# DDS_rev02.net
KiCad netlist of a schematic drawn in EAGLE
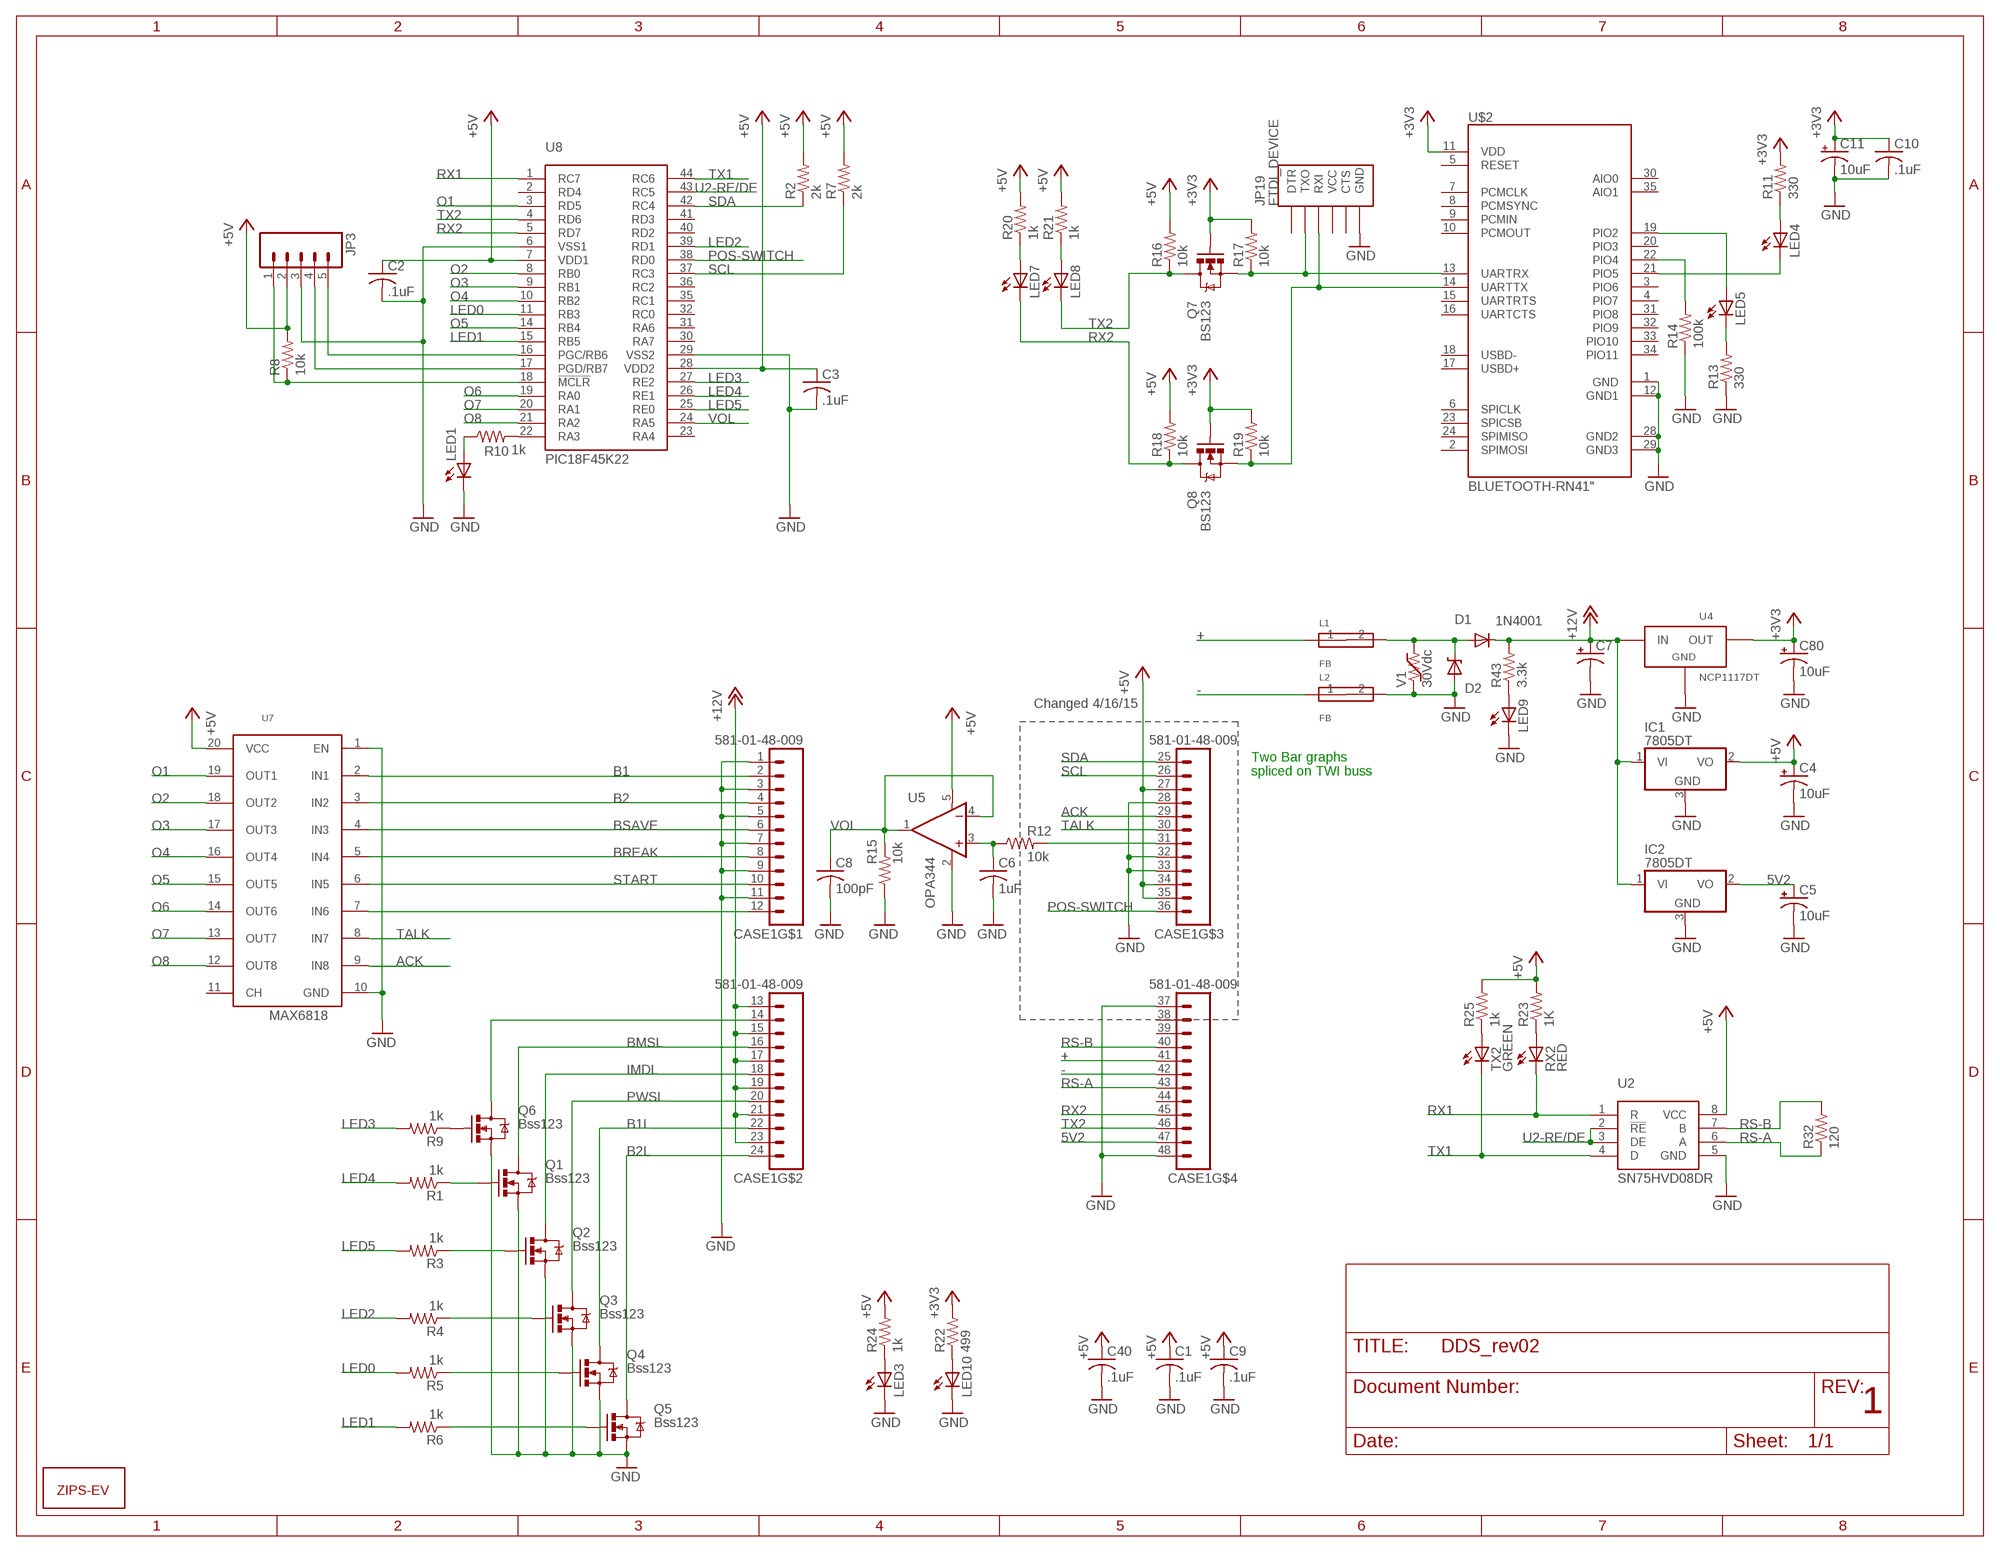
[diagram p0: schematic, sheet 1]

(export (version "E")
  (design (tool "Eeschema 10.0.6"))
  (components
    (comp (ref "C1")
      (value ".1uF")
      (footprint "eagle-import:C0805")
      (libsource (lib "eagle-import") (part "C-USC0805"))
    )
    (comp (ref "C2")
      (value ".1uF")
      (footprint "eagle-import:C0805")
      (libsource (lib "eagle-import") (part "C-USC0805"))
    )
    (comp (ref "C3")
      (value ".1uF")
      (footprint "eagle-import:C0805")
      (libsource (lib "eagle-import") (part "C-USC0805"))
    )
    (comp (ref "C4")
      (value "10uF")
      (footprint "eagle-import:POLC1206")
      (libsource (lib "eagle-import") (part "POLCAP"))
    )
    (comp (ref "C5")
      (value "10uF")
      (footprint "eagle-import:POLC1206")
      (libsource (lib "eagle-import") (part "POLCAP"))
    )
    (comp (ref "C6")
      (value "1uF")
      (footprint "eagle-import:C0805")
      (libsource (lib "eagle-import") (part "C-USC0805"))
    )
    (comp (ref "C7")
      (value "CAP_POL7343")
      (footprint "eagle-import:EIA7343")
      (libsource (lib "eagle-import") (part "CAP_POL7343"))
    )
    (comp (ref "C8")
      (value "100pF")
      (footprint "eagle-import:C0805")
      (libsource (lib "eagle-import") (part "C-USC0805"))
    )
    (comp (ref "C9")
      (value ".1uF")
      (footprint "eagle-import:C0805")
      (libsource (lib "eagle-import") (part "C-USC0805"))
    )
    (comp (ref "C10")
      (value ".1uF")
      (footprint "eagle-import:C0805")
      (libsource (lib "eagle-import") (part "C-USC0805"))
    )
    (comp (ref "C11")
      (value "10uF")
      (footprint "eagle-import:POLC1206")
      (libsource (lib "eagle-import") (part "POLCAP"))
    )
    (comp (ref "C40")
      (value ".1uF")
      (footprint "eagle-import:C0805")
      (libsource (lib "eagle-import") (part "C-USC0805"))
    )
    (comp (ref "C80")
      (value "10uF")
      (footprint "eagle-import:POLC1206")
      (libsource (lib "eagle-import") (part "POLCAP"))
    )
    (comp (ref "CASE1")
      (value "581-01-48-009")
      (footprint "eagle-import:581-01-48-009")
      (libsource (lib "eagle-import") (part "581-01-48-009"))
    )
    (comp (ref "D1")
      (value "1N4001")
      (footprint "eagle-import:SOD123")
      (libsource (lib "eagle-import") (part "DIODE-SOD123"))
    )
    (comp (ref "D2")
      (value "MM5Z30")
      (footprint "eagle-import:SOD-523F")
      (libsource (lib "eagle-import") (part "MM5Z30"))
    )
    (comp (ref "IC1")
      (value "7805DT")
      (footprint "eagle-import:TO252")
      (libsource (lib "eagle-import") (part "78DT05"))
    )
    (comp (ref "IC2")
      (value "7805DT")
      (footprint "eagle-import:TO252")
      (libsource (lib "eagle-import") (part "78DT05"))
    )
    (comp (ref "JP3")
      (value "M05LOCK_LONGPADS")
      (footprint "eagle-import:1X05_LOCK_LONGPADS")
      (libsource (lib "eagle-import") (part "M05LOCK_LONGPADS"))
    )
    (comp (ref "JP19")
      (value "FTDI_DEVICE")
      (footprint "eagle-import:FTDI_DEVICE_SIDE")
      (libsource (lib "eagle-import") (part "FTDI_DEVICE"))
    )
    (comp (ref "L1")
      (value "FB")
      (footprint "eagle-import:0603")
      (libsource (lib "eagle-import") (part "FERITEBEAD"))
    )
    (comp (ref "L2")
      (value "FB")
      (footprint "eagle-import:0603")
      (libsource (lib "eagle-import") (part "FERITEBEAD"))
    )
    (comp (ref "LED1")
      (value "LEDCHIP-LED0805")
      (footprint "eagle-import:CHIP-LED0805")
      (libsource (lib "eagle-import") (part "LEDCHIP-LED0805"))
    )
    (comp (ref "LED3")
      (value "LEDCHIP-LED0805")
      (footprint "eagle-import:CHIP-LED0805")
      (libsource (lib "eagle-import") (part "LEDCHIP-LED0805"))
    )
    (comp (ref "LED4")
      (value "LEDCHIP-LED0805")
      (footprint "eagle-import:CHIP-LED0805")
      (libsource (lib "eagle-import") (part "led_LEDCHIP-LED0805"))
    )
    (comp (ref "LED5")
      (value "LEDCHIP-LED0805")
      (footprint "eagle-import:CHIP-LED0805")
      (libsource (lib "eagle-import") (part "led_LEDCHIP-LED0805"))
    )
    (comp (ref "LED7")
      (value "LEDCHIP-LED0805")
      (footprint "eagle-import:CHIP-LED0805")
      (libsource (lib "eagle-import") (part "led_LEDCHIP-LED0805"))
    )
    (comp (ref "LED8")
      (value "LEDCHIP-LED0805")
      (footprint "eagle-import:CHIP-LED0805")
      (libsource (lib "eagle-import") (part "led_LEDCHIP-LED0805"))
    )
    (comp (ref "LED9")
      (value "LEDCHIP-LED0805")
      (footprint "eagle-import:CHIP-LED0805")
      (libsource (lib "eagle-import") (part "LEDCHIP-LED0805"))
    )
    (comp (ref "LED10")
      (value "LEDCHIP-LED0805")
      (footprint "eagle-import:CHIP-LED0805")
      (libsource (lib "eagle-import") (part "LEDCHIP-LED0805"))
    )
    (comp (ref "Q1")
      (value "Bss123")
      (footprint "eagle-import:SOT23")
      (libsource (lib "eagle-import") (part "MOSFET-NCHANNELBSS123LT1G"))
    )
    (comp (ref "Q2")
      (value "Bss123")
      (footprint "eagle-import:SOT23")
      (libsource (lib "eagle-import") (part "MOSFET-NCHANNELBSS123LT1G"))
    )
    (comp (ref "Q3")
      (value "Bss123")
      (footprint "eagle-import:SOT23")
      (libsource (lib "eagle-import") (part "MOSFET-NCHANNELBSS123LT1G"))
    )
    (comp (ref "Q4")
      (value "Bss123")
      (footprint "eagle-import:SOT23")
      (libsource (lib "eagle-import") (part "MOSFET-NCHANNELBSS123LT1G"))
    )
    (comp (ref "Q5")
      (value "Bss123")
      (footprint "eagle-import:SOT23")
      (libsource (lib "eagle-import") (part "MOSFET-NCHANNELBSS123LT1G"))
    )
    (comp (ref "Q6")
      (value "Bss123")
      (footprint "eagle-import:SOT23")
      (libsource (lib "eagle-import") (part "MOSFET-NCHANNELBSS123LT1G"))
    )
    (comp (ref "Q7")
      (value "BS123")
      (footprint "eagle-import:SOT23")
      (libsource (lib "eagle-import") (part "MOSFET-NCHANNELBSS123LT1G"))
    )
    (comp (ref "Q8")
      (value "BS123")
      (footprint "eagle-import:SOT23")
      (libsource (lib "eagle-import") (part "MOSFET-NCHANNELBSS123LT1G"))
    )
    (comp (ref "R1")
      (value "1k")
      (footprint "eagle-import:R0805")
      (libsource (lib "eagle-import") (part "R-US_R0805"))
    )
    (comp (ref "R2")
      (value "2k")
      (footprint "eagle-import:R0805")
      (libsource (lib "eagle-import") (part "R-US_R0805"))
    )
    (comp (ref "R3")
      (value "1k")
      (footprint "eagle-import:R0805")
      (libsource (lib "eagle-import") (part "R-US_R0805"))
    )
    (comp (ref "R4")
      (value "1k")
      (footprint "eagle-import:R0805")
      (libsource (lib "eagle-import") (part "R-US_R0805"))
    )
    (comp (ref "R5")
      (value "1k")
      (footprint "eagle-import:R0805")
      (libsource (lib "eagle-import") (part "R-US_R0805"))
    )
    (comp (ref "R6")
      (value "1k")
      (footprint "eagle-import:R0805")
      (libsource (lib "eagle-import") (part "R-US_R0805"))
    )
    (comp (ref "R7")
      (value "2k")
      (footprint "eagle-import:R0805")
      (libsource (lib "eagle-import") (part "R-US_R0805"))
    )
    (comp (ref "R8")
      (value "10k")
      (footprint "eagle-import:0805")
      (libsource (lib "eagle-import") (part "RESISTOR0805-RES"))
    )
    (comp (ref "R9")
      (value "1k")
      (footprint "eagle-import:R0805")
      (libsource (lib "eagle-import") (part "R-US_R0805"))
    )
    (comp (ref "R10")
      (value "1k")
      (footprint "eagle-import:R0805")
      (libsource (lib "eagle-import") (part "R-US_R0805"))
    )
    (comp (ref "R11")
      (value "330")
      (footprint "eagle-import:0805")
      (libsource (lib "eagle-import") (part "RESISTOR0805-RES"))
    )
    (comp (ref "R12")
      (value "10k")
      (footprint "eagle-import:R0805")
      (libsource (lib "eagle-import") (part "R-US_R0805"))
    )
    (comp (ref "R13")
      (value "330")
      (footprint "eagle-import:0805")
      (libsource (lib "eagle-import") (part "RESISTOR0805-RES"))
    )
    (comp (ref "R14")
      (value "100k")
      (footprint "eagle-import:0805")
      (libsource (lib "eagle-import") (part "RESISTOR0805-RES"))
    )
    (comp (ref "R15")
      (value "10k")
      (footprint "eagle-import:R0805")
      (libsource (lib "eagle-import") (part "R-US_R0805"))
    )
    (comp (ref "R16")
      (value "10k")
      (footprint "eagle-import:0805")
      (libsource (lib "eagle-import") (part "RESISTOR0805-RES"))
    )
    (comp (ref "R17")
      (value "10k")
      (footprint "eagle-import:0805")
      (libsource (lib "eagle-import") (part "RESISTOR0805-RES"))
    )
    (comp (ref "R18")
      (value "10k")
      (footprint "eagle-import:0805")
      (libsource (lib "eagle-import") (part "RESISTOR0805-RES"))
    )
    (comp (ref "R19")
      (value "10k")
      (footprint "eagle-import:0805")
      (libsource (lib "eagle-import") (part "RESISTOR0805-RES"))
    )
    (comp (ref "R20")
      (value "1k")
      (footprint "eagle-import:0805")
      (libsource (lib "eagle-import") (part "RESISTOR0805-RES"))
    )
    (comp (ref "R21")
      (value "1k")
      (footprint "eagle-import:0805")
      (libsource (lib "eagle-import") (part "RESISTOR0805-RES"))
    )
    (comp (ref "R22")
      (value "499")
      (footprint "eagle-import:R0805")
      (libsource (lib "eagle-import") (part "R-US_R0805"))
    )
    (comp (ref "R23")
      (value "1K")
      (footprint "eagle-import:R0805")
      (libsource (lib "eagle-import") (part "R-US_R0805"))
    )
    (comp (ref "R24")
      (value "1k")
      (footprint "eagle-import:R0805")
      (libsource (lib "eagle-import") (part "R-US_R0805"))
    )
    (comp (ref "R25")
      (value "1k")
      (footprint "eagle-import:R0805")
      (libsource (lib "eagle-import") (part "R-US_R0805"))
    )
    (comp (ref "R32")
      (value "120")
      (footprint "eagle-import:R0805")
      (libsource (lib "eagle-import") (part "R-US_R0805"))
    )
    (comp (ref "R43")
      (value "3.3k")
      (footprint "eagle-import:R0805")
      (libsource (lib "eagle-import") (part "R-US_R0805"))
    )
    (comp (ref "RX2")
      (value "RED")
      (footprint "eagle-import:CHIPLED_0805")
      (libsource (lib "eagle-import") (part "LEDCHIPLED_0805"))
    )
    (comp (ref "TX2")
      (value "GREEN")
      (footprint "eagle-import:CHIPLED_0805")
      (libsource (lib "eagle-import") (part "LEDCHIPLED_0805"))
    )
    (comp (ref "U$1")
      (value "LOGO")
      (footprint "eagle-import:L-L")
      (libsource (lib "eagle-import") (part "LOGO"))
    )
    (comp (ref "U$2")
      (value "BLUETOOTH-RN41\"")
      (footprint "eagle-import:RN41")
      (libsource (lib "eagle-import") (part "BLUETOOTH-RN41{dblquote}"))
    )
    (comp (ref "U2")
      (value "SN75HVD08DR")
      (footprint "eagle-import:SO-8")
      (libsource (lib "eagle-import") (part "SN75HVD08DR"))
    )
    (comp (ref "U4")
      (value "NCP1117DT")
      (footprint "eagle-import:DPAK")
      (libsource (lib "eagle-import") (part "NCP1117DT"))
    )
    (comp (ref "U5")
      (value "OPA344")
      (footprint "eagle-import:SOT23-5")
      (libsource (lib "eagle-import") (part "OPA344"))
    )
    (comp (ref "U7")
      (value "MAX6818")
      (footprint "eagle-import:SSOP-20")
      (libsource (lib "eagle-import") (part "MAX6818"))
    )
    (comp (ref "U8")
      (value "PIC18F45K22")
      (footprint "eagle-import:TQFP-44")
      (libsource (lib "eagle-import") (part "PIC18F45K22"))
    )
    (comp (ref "V1")
      (value "30Vdc")
      (footprint "eagle-import:0603")
      (libsource (lib "eagle-import") (part "VAR-RES"))
    )
  )
  (nets
    (net (code "1") (name "+3V3") (class "Default")
      (node (ref "C10") (pin "1") (pinfunction "1_1") (pintype "passive"))
      (node (ref "C11") (pin "1") (pinfunction "+_1") (pintype "passive"))
      (node (ref "C80") (pin "1") (pinfunction "+_1") (pintype "passive"))
      (node (ref "Q7") (pin "1") (pinfunction "G_1") (pintype "passive"))
      (node (ref "Q8") (pin "1") (pinfunction "G_1") (pintype "passive"))
      (node (ref "R11") (pin "2") (pinfunction "2_2") (pintype "passive"))
      (node (ref "R17") (pin "2") (pinfunction "2_2") (pintype "passive"))
      (node (ref "R19") (pin "2") (pinfunction "2_2") (pintype "passive"))
      (node (ref "R22") (pin "2") (pinfunction "2_2") (pintype "passive"))
      (node (ref "U$2") (pin "11") (pinfunction "VDD_11") (pintype "bidirectional"))
      (node (ref "U4") (pin "2") (pinfunction "OUT_2") (pintype "bidirectional"))
    )
    (net (code "2") (name "+5V") (class "Default")
      (node (ref "C1") (pin "1") (pinfunction "1_1") (pintype "passive"))
      (node (ref "C2") (pin "1") (pinfunction "1_1") (pintype "passive"))
      (node (ref "C3") (pin "1") (pinfunction "1_1") (pintype "passive"))
      (node (ref "C4") (pin "1") (pinfunction "+_1") (pintype "passive"))
      (node (ref "C40") (pin "1") (pinfunction "1_1") (pintype "passive"))
      (node (ref "C9") (pin "1") (pinfunction "1_1") (pintype "passive"))
      (node (ref "CASE1") (pin "27") (pinfunction "3_27") (pintype "passive"))
      (node (ref "CASE1") (pin "34") (pinfunction "10_34") (pintype "passive"))
      (node (ref "CASE1") (pin "35") (pinfunction "11_35") (pintype "passive"))
      (node (ref "IC1") (pin "2") (pinfunction "VO_2") (pintype "passive"))
      (node (ref "JP3") (pin "2") (pinfunction "2_2") (pintype "passive"))
      (node (ref "R16") (pin "2") (pinfunction "2_2") (pintype "passive"))
      (node (ref "R18") (pin "2") (pinfunction "2_2") (pintype "passive"))
      (node (ref "R2") (pin "2") (pinfunction "2_2") (pintype "passive"))
      (node (ref "R20") (pin "2") (pinfunction "2_2") (pintype "passive"))
      (node (ref "R21") (pin "2") (pinfunction "2_2") (pintype "passive"))
      (node (ref "R23") (pin "2") (pinfunction "2_2") (pintype "passive"))
      (node (ref "R24") (pin "2") (pinfunction "2_2") (pintype "passive"))
      (node (ref "R25") (pin "2") (pinfunction "2_2") (pintype "passive"))
      (node (ref "R7") (pin "2") (pinfunction "2_2") (pintype "passive"))
      (node (ref "R8") (pin "2") (pinfunction "2_2") (pintype "passive"))
      (node (ref "U2") (pin "8") (pinfunction "VCC_8") (pintype "bidirectional"))
      (node (ref "U5") (pin "5") (pinfunction "V+_5") (pintype "power_in"))
      (node (ref "U7") (pin "20") (pinfunction "VCC_20") (pintype "bidirectional"))
      (node (ref "U8") (pin "28") (pinfunction "VDD2_28") (pintype "bidirectional"))
      (node (ref "U8") (pin "7") (pinfunction "VDD1_7") (pintype "bidirectional"))
    )
    (net (code "3") (name "+12V") (class "Default")
      (node (ref "C7") (pin "A") (pinfunction "+_A") (pintype "passive"))
      (node (ref "CASE1") (pin "13") (pinfunction "1_13") (pintype "passive"))
      (node (ref "CASE1") (pin "15") (pinfunction "3_15") (pintype "passive"))
      (node (ref "CASE1") (pin "17") (pinfunction "5_17") (pintype "passive"))
      (node (ref "CASE1") (pin "19") (pinfunction "7_19") (pintype "passive"))
      (node (ref "CASE1") (pin "21") (pinfunction "9_21") (pintype "passive"))
      (node (ref "CASE1") (pin "23") (pinfunction "11_23") (pintype "passive"))
      (node (ref "D1") (pin "C") (pinfunction "C_C") (pintype "passive"))
      (node (ref "IC1") (pin "1") (pinfunction "VI_1") (pintype "input"))
      (node (ref "IC2") (pin "1") (pinfunction "VI_1") (pintype "input"))
      (node (ref "R43") (pin "2") (pinfunction "2_2") (pintype "passive"))
      (node (ref "U4") (pin "3") (pinfunction "IN_3") (pintype "bidirectional"))
    )
    (net (code "4") (name "/+") (class "Default")
      (node (ref "CASE1") (pin "41") (pinfunction "5_41") (pintype "passive"))
      (node (ref "L1") (pin "1") (pinfunction "P$1_1") (pintype "bidirectional"))
    )
    (net (code "5") (name "/-") (class "Default")
      (node (ref "CASE1") (pin "42") (pinfunction "6_42") (pintype "passive"))
      (node (ref "L2") (pin "1") (pinfunction "P$1_1") (pintype "bidirectional"))
    )
    (net (code "6") (name "/5V2") (class "Default")
      (node (ref "C5") (pin "1") (pinfunction "+_1") (pintype "passive"))
      (node (ref "CASE1") (pin "47") (pinfunction "11_47") (pintype "passive"))
      (node (ref "IC2") (pin "2") (pinfunction "VO_2") (pintype "passive"))
    )
    (net (code "7") (name "/ACK") (class "Default")
      (node (ref "CASE1") (pin "29") (pinfunction "5_29") (pintype "passive"))
      (node (ref "U7") (pin "9") (pinfunction "IN8_9") (pintype "bidirectional"))
    )
    (net (code "8") (name "/B1") (class "Default")
      (node (ref "CASE1") (pin "2") (pinfunction "2_2") (pintype "passive"))
      (node (ref "U7") (pin "2") (pinfunction "IN1_2") (pintype "bidirectional"))
    )
    (net (code "9") (name "/B1L") (class "Default")
      (node (ref "CASE1") (pin "22") (pinfunction "10_22") (pintype "passive"))
      (node (ref "Q4") (pin "3") (pinfunction "D_3") (pintype "passive"))
    )
    (net (code "10") (name "/B2") (class "Default")
      (node (ref "CASE1") (pin "4") (pinfunction "4_4") (pintype "passive"))
      (node (ref "U7") (pin "3") (pinfunction "IN2_3") (pintype "bidirectional"))
    )
    (net (code "11") (name "/B2L") (class "Default")
      (node (ref "CASE1") (pin "24") (pinfunction "12_24") (pintype "passive"))
      (node (ref "Q5") (pin "3") (pinfunction "D_3") (pintype "passive"))
    )
    (net (code "12") (name "/BMSL") (class "Default")
      (node (ref "CASE1") (pin "16") (pinfunction "4_16") (pintype "passive"))
      (node (ref "Q1") (pin "3") (pinfunction "D_3") (pintype "passive"))
    )
    (net (code "13") (name "/BREAK") (class "Default")
      (node (ref "CASE1") (pin "8") (pinfunction "8_8") (pintype "passive"))
      (node (ref "U7") (pin "5") (pinfunction "IN4_5") (pintype "bidirectional"))
    )
    (net (code "14") (name "/BSAVE") (class "Default")
      (node (ref "CASE1") (pin "6") (pinfunction "6_6") (pintype "passive"))
      (node (ref "U7") (pin "4") (pinfunction "IN3_4") (pintype "bidirectional"))
    )
    (net (code "15") (name "/IMDL") (class "Default")
      (node (ref "CASE1") (pin "18") (pinfunction "6_18") (pintype "passive"))
      (node (ref "Q2") (pin "3") (pinfunction "D_3") (pintype "passive"))
    )
    (net (code "16") (name "/LED0") (class "Default")
      (node (ref "R5") (pin "2") (pinfunction "2_2") (pintype "passive"))
      (node (ref "U8") (pin "11") (pinfunction "RB3_11") (pintype "bidirectional"))
    )
    (net (code "17") (name "/LED1") (class "Default")
      (node (ref "R6") (pin "2") (pinfunction "2_2") (pintype "passive"))
      (node (ref "U8") (pin "15") (pinfunction "RB5_15") (pintype "bidirectional"))
    )
    (net (code "18") (name "/LED2") (class "Default")
      (node (ref "R4") (pin "2") (pinfunction "2_2") (pintype "passive"))
      (node (ref "U8") (pin "39") (pinfunction "RD1_39") (pintype "bidirectional"))
    )
    (net (code "19") (name "/LED3") (class "Default")
      (node (ref "R9") (pin "2") (pinfunction "2_2") (pintype "passive"))
      (node (ref "U8") (pin "27") (pinfunction "RE2_27") (pintype "bidirectional"))
    )
    (net (code "20") (name "/LED4") (class "Default")
      (node (ref "R1") (pin "2") (pinfunction "2_2") (pintype "passive"))
      (node (ref "U8") (pin "26") (pinfunction "RE1_26") (pintype "bidirectional"))
    )
    (net (code "21") (name "/LED5") (class "Default")
      (node (ref "R3") (pin "2") (pinfunction "2_2") (pintype "passive"))
      (node (ref "U8") (pin "25") (pinfunction "RE0_25") (pintype "bidirectional"))
    )
    (net (code "22") (name "/O1") (class "Default")
      (node (ref "U7") (pin "19") (pinfunction "OUT1_19") (pintype "bidirectional"))
      (node (ref "U8") (pin "3") (pinfunction "RD5_3") (pintype "bidirectional"))
    )
    (net (code "23") (name "/O2") (class "Default")
      (node (ref "U7") (pin "18") (pinfunction "OUT2_18") (pintype "bidirectional"))
      (node (ref "U8") (pin "8") (pinfunction "RB0_8") (pintype "bidirectional"))
    )
    (net (code "24") (name "/O3") (class "Default")
      (node (ref "U7") (pin "17") (pinfunction "OUT3_17") (pintype "bidirectional"))
      (node (ref "U8") (pin "9") (pinfunction "RB1_9") (pintype "bidirectional"))
    )
    (net (code "25") (name "/O4") (class "Default")
      (node (ref "U7") (pin "16") (pinfunction "OUT4_16") (pintype "bidirectional"))
      (node (ref "U8") (pin "10") (pinfunction "RB2_10") (pintype "bidirectional"))
    )
    (net (code "26") (name "/O5") (class "Default")
      (node (ref "U7") (pin "15") (pinfunction "OUT5_15") (pintype "bidirectional"))
      (node (ref "U8") (pin "14") (pinfunction "RB4_14") (pintype "bidirectional"))
    )
    (net (code "27") (name "/O6") (class "Default")
      (node (ref "U7") (pin "14") (pinfunction "OUT6_14") (pintype "bidirectional"))
      (node (ref "U8") (pin "19") (pinfunction "RA0_19") (pintype "bidirectional"))
    )
    (net (code "28") (name "/O7") (class "Default")
      (node (ref "U7") (pin "13") (pinfunction "OUT7_13") (pintype "bidirectional"))
      (node (ref "U8") (pin "20") (pinfunction "RA1_20") (pintype "bidirectional"))
    )
    (net (code "29") (name "/O8") (class "Default")
      (node (ref "U7") (pin "12") (pinfunction "OUT8_12") (pintype "bidirectional"))
      (node (ref "U8") (pin "21") (pinfunction "RA2_21") (pintype "bidirectional"))
    )
    (net (code "30") (name "/POS-SWITCH") (class "Default")
      (node (ref "CASE1") (pin "36") (pinfunction "12_36") (pintype "passive"))
      (node (ref "U8") (pin "38") (pinfunction "RD0_38") (pintype "bidirectional"))
    )
    (net (code "31") (name "/PWSL") (class "Default")
      (node (ref "CASE1") (pin "20") (pinfunction "8_20") (pintype "passive"))
      (node (ref "Q3") (pin "3") (pinfunction "D_3") (pintype "passive"))
    )
    (net (code "32") (name "/RS-A") (class "Default")
      (node (ref "CASE1") (pin "43") (pinfunction "7_43") (pintype "passive"))
      (node (ref "R32") (pin "1") (pinfunction "1_1") (pintype "passive"))
      (node (ref "U2") (pin "6") (pinfunction "A_6") (pintype "bidirectional"))
    )
    (net (code "33") (name "/RS-B") (class "Default")
      (node (ref "CASE1") (pin "40") (pinfunction "4_40") (pintype "passive"))
      (node (ref "R32") (pin "2") (pinfunction "2_2") (pintype "passive"))
      (node (ref "U2") (pin "7") (pinfunction "B_7") (pintype "bidirectional"))
    )
    (net (code "34") (name "/RX1") (class "Default")
      (node (ref "RX2") (pin "C") (pinfunction "C_C") (pintype "passive"))
      (node (ref "U2") (pin "1") (pinfunction "R_1") (pintype "bidirectional"))
      (node (ref "U8") (pin "1") (pinfunction "RC7_1") (pintype "bidirectional"))
    )
    (net (code "35") (name "/RX2") (class "Default")
      (node (ref "CASE1") (pin "45") (pinfunction "9_45") (pintype "passive"))
      (node (ref "LED7") (pin "C") (pinfunction "C_C") (pintype "passive"))
      (node (ref "Q8") (pin "3") (pinfunction "D_3") (pintype "passive"))
      (node (ref "R18") (pin "1") (pinfunction "1_1") (pintype "passive"))
      (node (ref "U8") (pin "5") (pinfunction "RD7_5") (pintype "bidirectional"))
    )
    (net (code "36") (name "/SCL") (class "Default")
      (node (ref "CASE1") (pin "26") (pinfunction "2_26") (pintype "passive"))
      (node (ref "R7") (pin "1") (pinfunction "1_1") (pintype "passive"))
      (node (ref "U8") (pin "37") (pinfunction "RC3_37") (pintype "bidirectional"))
    )
    (net (code "37") (name "/SDA") (class "Default")
      (node (ref "CASE1") (pin "25") (pinfunction "1_25") (pintype "passive"))
      (node (ref "R2") (pin "1") (pinfunction "1_1") (pintype "passive"))
      (node (ref "U8") (pin "42") (pinfunction "RC4_42") (pintype "bidirectional"))
    )
    (net (code "38") (name "/START") (class "Default")
      (node (ref "CASE1") (pin "10") (pinfunction "10_10") (pintype "passive"))
      (node (ref "U7") (pin "6") (pinfunction "IN5_6") (pintype "bidirectional"))
    )
    (net (code "39") (name "/TALK") (class "Default")
      (node (ref "CASE1") (pin "30") (pinfunction "6_30") (pintype "passive"))
      (node (ref "U7") (pin "8") (pinfunction "IN7_8") (pintype "bidirectional"))
    )
    (net (code "40") (name "/TX1") (class "Default")
      (node (ref "TX2") (pin "C") (pinfunction "C_C") (pintype "passive"))
      (node (ref "U2") (pin "4") (pinfunction "D_4") (pintype "bidirectional"))
      (node (ref "U8") (pin "44") (pinfunction "RC6_44") (pintype "bidirectional"))
    )
    (net (code "41") (name "/TX2") (class "Default")
      (node (ref "CASE1") (pin "46") (pinfunction "10_46") (pintype "passive"))
      (node (ref "LED8") (pin "C") (pinfunction "C_C") (pintype "passive"))
      (node (ref "Q7") (pin "3") (pinfunction "D_3") (pintype "passive"))
      (node (ref "R16") (pin "1") (pinfunction "1_1") (pintype "passive"))
      (node (ref "U8") (pin "4") (pinfunction "RD6_4") (pintype "bidirectional"))
    )
    (net (code "42") (name "/U2-RE{slash}DE") (class "Default")
      (node (ref "U2") (pin "2") (pinfunction "~{RE}_2") (pintype "bidirectional"))
      (node (ref "U2") (pin "3") (pinfunction "DE_3") (pintype "bidirectional"))
      (node (ref "U8") (pin "43") (pinfunction "RC5_43") (pintype "bidirectional"))
    )
    (net (code "43") (name "/VOL") (class "Default")
      (node (ref "C8") (pin "1") (pinfunction "1_1") (pintype "passive"))
      (node (ref "R15") (pin "2") (pinfunction "2_2") (pintype "passive"))
      (node (ref "U5") (pin "1") (pinfunction "OUT_1") (pintype "output"))
      (node (ref "U5") (pin "4") (pinfunction "-IN_4") (pintype "input"))
      (node (ref "U8") (pin "24") (pinfunction "RA5_24") (pintype "bidirectional"))
    )
    (net (code "44") (name "GND") (class "Default")
      (node (ref "C1") (pin "2") (pinfunction "2_2") (pintype "passive"))
      (node (ref "C10") (pin "2") (pinfunction "2_2") (pintype "passive"))
      (node (ref "C11") (pin "2") (pinfunction "-_2") (pintype "passive"))
      (node (ref "C2") (pin "2") (pinfunction "2_2") (pintype "passive"))
      (node (ref "C3") (pin "2") (pinfunction "2_2") (pintype "passive"))
      (node (ref "C4") (pin "2") (pinfunction "-_2") (pintype "passive"))
      (node (ref "C40") (pin "2") (pinfunction "2_2") (pintype "passive"))
      (node (ref "C5") (pin "2") (pinfunction "-_2") (pintype "passive"))
      (node (ref "C6") (pin "2") (pinfunction "2_2") (pintype "passive"))
      (node (ref "C7") (pin "C") (pinfunction "-_C") (pintype "passive"))
      (node (ref "C8") (pin "2") (pinfunction "2_2") (pintype "passive"))
      (node (ref "C80") (pin "2") (pinfunction "-_2") (pintype "passive"))
      (node (ref "C9") (pin "2") (pinfunction "2_2") (pintype "passive"))
      (node (ref "CASE1") (pin "1") (pinfunction "1_1") (pintype "passive"))
      (node (ref "CASE1") (pin "11") (pinfunction "11_11") (pintype "passive"))
      (node (ref "CASE1") (pin "28") (pinfunction "4_28") (pintype "passive"))
      (node (ref "CASE1") (pin "3") (pinfunction "3_3") (pintype "passive"))
      (node (ref "CASE1") (pin "32") (pinfunction "8_32") (pintype "passive"))
      (node (ref "CASE1") (pin "33") (pinfunction "9_33") (pintype "passive"))
      (node (ref "CASE1") (pin "37") (pinfunction "1_37") (pintype "passive"))
      (node (ref "CASE1") (pin "48") (pinfunction "12_48") (pintype "passive"))
      (node (ref "CASE1") (pin "5") (pinfunction "5_5") (pintype "passive"))
      (node (ref "CASE1") (pin "7") (pinfunction "7_7") (pintype "passive"))
      (node (ref "CASE1") (pin "9") (pinfunction "9_9") (pintype "passive"))
      (node (ref "D2") (pin "A") (pinfunction "A_A") (pintype "passive"))
      (node (ref "IC1") (pin "3") (pinfunction "GND_3") (pintype "passive"))
      (node (ref "IC2") (pin "3") (pinfunction "GND_3") (pintype "passive"))
      (node (ref "JP19") (pin "P$6") (pinfunction "GND_P$6") (pintype "bidirectional"))
      (node (ref "JP3") (pin "3") (pinfunction "3_3") (pintype "passive"))
      (node (ref "L2") (pin "2") (pinfunction "P$2_2") (pintype "bidirectional"))
      (node (ref "LED1") (pin "C") (pinfunction "C_C") (pintype "passive"))
      (node (ref "LED10") (pin "C") (pinfunction "C_C") (pintype "passive"))
      (node (ref "LED3") (pin "C") (pinfunction "C_C") (pintype "passive"))
      (node (ref "LED9") (pin "C") (pinfunction "C_C") (pintype "passive"))
      (node (ref "Q1") (pin "2") (pinfunction "S_2") (pintype "passive"))
      (node (ref "Q2") (pin "2") (pinfunction "S_2") (pintype "passive"))
      (node (ref "Q3") (pin "2") (pinfunction "S_2") (pintype "passive"))
      (node (ref "Q4") (pin "2") (pinfunction "S_2") (pintype "passive"))
      (node (ref "Q5") (pin "2") (pinfunction "S_2") (pintype "passive"))
      (node (ref "Q6") (pin "2") (pinfunction "S_2") (pintype "passive"))
      (node (ref "R13") (pin "1") (pinfunction "1_1") (pintype "passive"))
      (node (ref "R14") (pin "1") (pinfunction "1_1") (pintype "passive"))
      (node (ref "R15") (pin "1") (pinfunction "1_1") (pintype "passive"))
      (node (ref "U$2") (pin "1") (pinfunction "GND_1") (pintype "bidirectional"))
      (node (ref "U$2") (pin "12") (pinfunction "GND1_12") (pintype "bidirectional"))
      (node (ref "U$2") (pin "28") (pinfunction "GND2_28") (pintype "bidirectional"))
      (node (ref "U$2") (pin "29") (pinfunction "GND3_29") (pintype "bidirectional"))
      (node (ref "U2") (pin "5") (pinfunction "GND_5") (pintype "bidirectional"))
      (node (ref "U4") (pin "1") (pinfunction "GND_1") (pintype "bidirectional"))
      (node (ref "U5") (pin "2") (pinfunction "V-_2") (pintype "power_in"))
      (node (ref "U7") (pin "1") (pinfunction "EN_1") (pintype "bidirectional"))
      (node (ref "U7") (pin "10") (pinfunction "GND_10") (pintype "bidirectional"))
      (node (ref "U8") (pin "29") (pinfunction "VSS2_29") (pintype "bidirectional"))
      (node (ref "U8") (pin "6") (pinfunction "VSS1_6") (pintype "bidirectional"))
      (node (ref "V1") (pin "1") (pinfunction "1_1") (pintype "passive"))
    )
    (net (code "45") (name "Net-(CASE1B-2)") (class "Default")
      (node (ref "CASE1") (pin "14") (pinfunction "2_14") (pintype "passive"))
      (node (ref "Q6") (pin "3") (pinfunction "D_3") (pintype "passive"))
    )
    (net (code "46") (name "Net-(CASE1C-7)") (class "Default")
      (node (ref "CASE1") (pin "31") (pinfunction "7_31") (pintype "passive"))
      (node (ref "R12") (pin "2") (pinfunction "2_2") (pintype "passive"))
    )
    (net (code "47") (name "Net-(JP19-RXI)") (class "Default")
      (node (ref "JP19") (pin "P$3") (pinfunction "RXI_P$3") (pintype "bidirectional"))
      (node (ref "Q8") (pin "2") (pinfunction "S_2") (pintype "passive"))
      (node (ref "R19") (pin "1") (pinfunction "1_1") (pintype "passive"))
      (node (ref "U$2") (pin "14") (pinfunction "UARTTX_14") (pintype "bidirectional"))
    )
    (net (code "48") (name "Net-(JP19-TXO)") (class "Default")
      (node (ref "JP19") (pin "P$2") (pinfunction "TXO_P$2") (pintype "bidirectional"))
      (node (ref "Q7") (pin "2") (pinfunction "S_2") (pintype "passive"))
      (node (ref "R17") (pin "1") (pinfunction "1_1") (pintype "passive"))
      (node (ref "U$2") (pin "13") (pinfunction "UARTRX_13") (pintype "bidirectional"))
    )
    (net (code "49") (name "Net-(L1-P$2)") (class "Default")
      (node (ref "D1") (pin "A") (pinfunction "A_A") (pintype "passive"))
      (node (ref "D2") (pin "C") (pinfunction "C_C") (pintype "passive"))
      (node (ref "L1") (pin "2") (pinfunction "P$2_2") (pintype "bidirectional"))
      (node (ref "V1") (pin "2") (pinfunction "2_2") (pintype "passive"))
    )
    (net (code "50") (name "Net-(LED1-PadA)") (class "Default")
      (node (ref "LED1") (pin "A") (pinfunction "A_A") (pintype "passive"))
      (node (ref "R10") (pin "1") (pinfunction "1_1") (pintype "passive"))
    )
    (net (code "51") (name "Net-(LED3-PadA)") (class "Default")
      (node (ref "LED3") (pin "A") (pinfunction "A_A") (pintype "passive"))
      (node (ref "R24") (pin "1") (pinfunction "1_1") (pintype "passive"))
    )
    (net (code "52") (name "Net-(LED4-PadA)") (class "Default")
      (node (ref "LED4") (pin "A") (pinfunction "A_A") (pintype "passive"))
      (node (ref "R11") (pin "1") (pinfunction "1_1") (pintype "passive"))
    )
    (net (code "53") (name "Net-(LED5-PadC)") (class "Default")
      (node (ref "LED5") (pin "C") (pinfunction "C_C") (pintype "passive"))
      (node (ref "R13") (pin "2") (pinfunction "2_2") (pintype "passive"))
    )
    (net (code "54") (name "Net-(LED7-PadA)") (class "Default")
      (node (ref "LED7") (pin "A") (pinfunction "A_A") (pintype "passive"))
      (node (ref "R20") (pin "1") (pinfunction "1_1") (pintype "passive"))
    )
    (net (code "55") (name "Net-(LED8-PadA)") (class "Default")
      (node (ref "LED8") (pin "A") (pinfunction "A_A") (pintype "passive"))
      (node (ref "R21") (pin "1") (pinfunction "1_1") (pintype "passive"))
    )
    (net (code "56") (name "Net-(LED9-PadA)") (class "Default")
      (node (ref "LED9") (pin "A") (pinfunction "A_A") (pintype "passive"))
      (node (ref "R43") (pin "1") (pinfunction "1_1") (pintype "passive"))
    )
    (net (code "57") (name "Net-(LED10-PadA)") (class "Default")
      (node (ref "LED10") (pin "A") (pinfunction "A_A") (pintype "passive"))
      (node (ref "R22") (pin "1") (pinfunction "1_1") (pintype "passive"))
    )
    (net (code "58") (name "Net-(Q1-G)") (class "Default")
      (node (ref "Q1") (pin "1") (pinfunction "G_1") (pintype "passive"))
      (node (ref "R1") (pin "1") (pinfunction "1_1") (pintype "passive"))
    )
    (net (code "59") (name "Net-(Q2-G)") (class "Default")
      (node (ref "Q2") (pin "1") (pinfunction "G_1") (pintype "passive"))
      (node (ref "R3") (pin "1") (pinfunction "1_1") (pintype "passive"))
    )
    (net (code "60") (name "Net-(Q3-G)") (class "Default")
      (node (ref "Q3") (pin "1") (pinfunction "G_1") (pintype "passive"))
      (node (ref "R4") (pin "1") (pinfunction "1_1") (pintype "passive"))
    )
    (net (code "61") (name "Net-(Q4-G)") (class "Default")
      (node (ref "Q4") (pin "1") (pinfunction "G_1") (pintype "passive"))
      (node (ref "R5") (pin "1") (pinfunction "1_1") (pintype "passive"))
    )
    (net (code "62") (name "Net-(Q5-G)") (class "Default")
      (node (ref "Q5") (pin "1") (pinfunction "G_1") (pintype "passive"))
      (node (ref "R6") (pin "1") (pinfunction "1_1") (pintype "passive"))
    )
    (net (code "63") (name "Net-(Q6-G)") (class "Default")
      (node (ref "Q6") (pin "1") (pinfunction "G_1") (pintype "passive"))
      (node (ref "R9") (pin "1") (pinfunction "1_1") (pintype "passive"))
    )
    (net (code "64") (name "Net-(R23-Pad1)") (class "Default")
      (node (ref "R23") (pin "1") (pinfunction "1_1") (pintype "passive"))
      (node (ref "RX2") (pin "A") (pinfunction "A_A") (pintype "passive"))
    )
    (net (code "65") (name "Net-(R25-Pad1)") (class "Default")
      (node (ref "R25") (pin "1") (pinfunction "1_1") (pintype "passive"))
      (node (ref "TX2") (pin "A") (pinfunction "A_A") (pintype "passive"))
    )
    (net (code "66") (name "Net-(U$2-PIO2)") (class "Default")
      (node (ref "LED5") (pin "A") (pinfunction "A_A") (pintype "passive"))
      (node (ref "U$2") (pin "19") (pinfunction "PIO2_19") (pintype "bidirectional"))
    )
    (net (code "67") (name "Net-(U$2-PIO4)") (class "Default")
      (node (ref "R14") (pin "2") (pinfunction "2_2") (pintype "passive"))
      (node (ref "U$2") (pin "22") (pinfunction "PIO4_22") (pintype "bidirectional"))
    )
    (net (code "68") (name "Net-(U$2-PIO5)") (class "Default")
      (node (ref "LED4") (pin "C") (pinfunction "C_C") (pintype "passive"))
      (node (ref "U$2") (pin "21") (pinfunction "PIO5_21") (pintype "bidirectional"))
    )
    (net (code "69") (name "Net-(U5-+IN)") (class "Default")
      (node (ref "C6") (pin "1") (pinfunction "1_1") (pintype "passive"))
      (node (ref "R12") (pin "1") (pinfunction "1_1") (pintype "passive"))
      (node (ref "U5") (pin "3") (pinfunction "+IN_3") (pintype "input"))
    )
    (net (code "70") (name "Net-(U7-IN6)") (class "Default")
      (node (ref "CASE1") (pin "12") (pinfunction "12_12") (pintype "passive"))
      (node (ref "U7") (pin "7") (pinfunction "IN6_7") (pintype "bidirectional"))
    )
    (net (code "71") (name "Net-(U8-PGC{slash}RB6)") (class "Default")
      (node (ref "JP3") (pin "5") (pinfunction "5_5") (pintype "passive"))
      (node (ref "U8") (pin "16") (pinfunction "PGC/RB6_16") (pintype "bidirectional"))
    )
    (net (code "72") (name "Net-(U8-PGD{slash}RB7)") (class "Default")
      (node (ref "JP3") (pin "4") (pinfunction "4_4") (pintype "passive"))
      (node (ref "U8") (pin "17") (pinfunction "PGD/RB7_17") (pintype "bidirectional"))
    )
    (net (code "73") (name "Net-(U8-RA3)") (class "Default")
      (node (ref "R10") (pin "2") (pinfunction "2_2") (pintype "passive"))
      (node (ref "U8") (pin "22") (pinfunction "RA3_22") (pintype "bidirectional"))
    )
    (net (code "74") (name "Net-(U8-~{MCLR})") (class "Default")
      (node (ref "JP3") (pin "1") (pinfunction "1_1") (pintype "passive"))
      (node (ref "R8") (pin "1") (pinfunction "1_1") (pintype "passive"))
      (node (ref "U8") (pin "18") (pinfunction "~{MCLR}_18") (pintype "bidirectional"))
    )
    (net (code "75") (name "unconnected-(CASE1D-2-Pad38)") (class "Default")
      (node (ref "CASE1") (pin "38") (pinfunction "2_38") (pintype "passive"))
    )
    (net (code "76") (name "unconnected-(CASE1D-3-Pad39)") (class "Default")
      (node (ref "CASE1") (pin "39") (pinfunction "3_39") (pintype "passive"))
    )
    (net (code "77") (name "unconnected-(CASE1D-8-Pad44)") (class "Default")
      (node (ref "CASE1") (pin "44") (pinfunction "8_44") (pintype "passive"))
    )
    (net (code "78") (name "unconnected-(JP19-CTS-PadP$5)") (class "Default")
      (node (ref "JP19") (pin "P$5") (pinfunction "CTS_P$5") (pintype "bidirectional"))
    )
    (net (code "79") (name "unconnected-(JP19-DTR-PadP$1)") (class "Default")
      (node (ref "JP19") (pin "P$1") (pinfunction "DTR_P$1") (pintype "bidirectional"))
    )
    (net (code "80") (name "unconnected-(JP19-VCC-PadP$4)") (class "Default")
      (node (ref "JP19") (pin "P$4") (pinfunction "VCC_P$4") (pintype "bidirectional"))
    )
    (net (code "81") (name "unconnected-(U$2-AIO0-Pad30)") (class "Default")
      (node (ref "U$2") (pin "30") (pinfunction "AIO0_30") (pintype "bidirectional"))
    )
    (net (code "82") (name "unconnected-(U$2-AIO1-Pad35)") (class "Default")
      (node (ref "U$2") (pin "35") (pinfunction "AIO1_35") (pintype "bidirectional"))
    )
    (net (code "83") (name "unconnected-(U$2-PCMCLK-Pad7)") (class "Default")
      (node (ref "U$2") (pin "7") (pinfunction "PCMCLK_7") (pintype "bidirectional"))
    )
    (net (code "84") (name "unconnected-(U$2-PCMIN-Pad9)") (class "Default")
      (node (ref "U$2") (pin "9") (pinfunction "PCMIN_9") (pintype "bidirectional"))
    )
    (net (code "85") (name "unconnected-(U$2-PCMOUT-Pad10)") (class "Default")
      (node (ref "U$2") (pin "10") (pinfunction "PCMOUT_10") (pintype "bidirectional"))
    )
    (net (code "86") (name "unconnected-(U$2-PCMSYNC-Pad8)") (class "Default")
      (node (ref "U$2") (pin "8") (pinfunction "PCMSYNC_8") (pintype "bidirectional"))
    )
    (net (code "87") (name "unconnected-(U$2-PIO3-Pad20)") (class "Default")
      (node (ref "U$2") (pin "20") (pinfunction "PIO3_20") (pintype "bidirectional"))
    )
    (net (code "88") (name "unconnected-(U$2-PIO6-Pad3)") (class "Default")
      (node (ref "U$2") (pin "3") (pinfunction "PIO6_3") (pintype "bidirectional"))
    )
    (net (code "89") (name "unconnected-(U$2-PIO7-Pad4)") (class "Default")
      (node (ref "U$2") (pin "4") (pinfunction "PIO7_4") (pintype "bidirectional"))
    )
    (net (code "90") (name "unconnected-(U$2-PIO8-Pad31)") (class "Default")
      (node (ref "U$2") (pin "31") (pinfunction "PIO8_31") (pintype "bidirectional"))
    )
    (net (code "91") (name "unconnected-(U$2-PIO9-Pad32)") (class "Default")
      (node (ref "U$2") (pin "32") (pinfunction "PIO9_32") (pintype "bidirectional"))
    )
    (net (code "92") (name "unconnected-(U$2-PIO10-Pad33)") (class "Default")
      (node (ref "U$2") (pin "33") (pinfunction "PIO10_33") (pintype "bidirectional"))
    )
    (net (code "93") (name "unconnected-(U$2-PIO11-Pad34)") (class "Default")
      (node (ref "U$2") (pin "34") (pinfunction "PIO11_34") (pintype "bidirectional"))
    )
    (net (code "94") (name "unconnected-(U$2-RESET-Pad5)") (class "Default")
      (node (ref "U$2") (pin "5") (pinfunction "RESET_5") (pintype "bidirectional"))
    )
    (net (code "95") (name "unconnected-(U$2-SPICLK-Pad6)") (class "Default")
      (node (ref "U$2") (pin "6") (pinfunction "SPICLK_6") (pintype "bidirectional"))
    )
    (net (code "96") (name "unconnected-(U$2-SPICSB-Pad23)") (class "Default")
      (node (ref "U$2") (pin "23") (pinfunction "SPICSB_23") (pintype "bidirectional"))
    )
    (net (code "97") (name "unconnected-(U$2-SPIMISO-Pad24)") (class "Default")
      (node (ref "U$2") (pin "24") (pinfunction "SPIMISO_24") (pintype "bidirectional"))
    )
    (net (code "98") (name "unconnected-(U$2-SPIMOSI-Pad2)") (class "Default")
      (node (ref "U$2") (pin "2") (pinfunction "SPIMOSI_2") (pintype "bidirectional"))
    )
    (net (code "99") (name "unconnected-(U$2-UARTCTS-Pad16)") (class "Default")
      (node (ref "U$2") (pin "16") (pinfunction "UARTCTS_16") (pintype "bidirectional"))
    )
    (net (code "100") (name "unconnected-(U$2-UARTRTS-Pad15)") (class "Default")
      (node (ref "U$2") (pin "15") (pinfunction "UARTRTS_15") (pintype "bidirectional"))
    )
    (net (code "101") (name "unconnected-(U$2-USBD+-Pad17)") (class "Default")
      (node (ref "U$2") (pin "17") (pinfunction "USBD+_17") (pintype "bidirectional"))
    )
    (net (code "102") (name "unconnected-(U$2-USBD--Pad18)") (class "Default")
      (node (ref "U$2") (pin "18") (pinfunction "USBD-_18") (pintype "bidirectional"))
    )
    (net (code "103") (name "unconnected-(U7-CH-Pad11)") (class "Default")
      (node (ref "U7") (pin "11") (pinfunction "CH_11") (pintype "bidirectional"))
    )
    (net (code "104") (name "unconnected-(U8-RA4-Pad23)") (class "Default")
      (node (ref "U8") (pin "23") (pinfunction "RA4_23") (pintype "bidirectional"))
    )
    (net (code "105") (name "unconnected-(U8-RA6-Pad31)") (class "Default")
      (node (ref "U8") (pin "31") (pinfunction "RA6_31") (pintype "bidirectional"))
    )
    (net (code "106") (name "unconnected-(U8-RA7-Pad30)") (class "Default")
      (node (ref "U8") (pin "30") (pinfunction "RA7_30") (pintype "bidirectional"))
    )
    (net (code "107") (name "unconnected-(U8-RC0-Pad32)") (class "Default")
      (node (ref "U8") (pin "32") (pinfunction "RC0_32") (pintype "bidirectional"))
    )
    (net (code "108") (name "unconnected-(U8-RC1-Pad35)") (class "Default")
      (node (ref "U8") (pin "35") (pinfunction "RC1_35") (pintype "bidirectional"))
    )
    (net (code "109") (name "unconnected-(U8-RC2-Pad36)") (class "Default")
      (node (ref "U8") (pin "36") (pinfunction "RC2_36") (pintype "bidirectional"))
    )
    (net (code "110") (name "unconnected-(U8-RD2-Pad40)") (class "Default")
      (node (ref "U8") (pin "40") (pinfunction "RD2_40") (pintype "bidirectional"))
    )
    (net (code "111") (name "unconnected-(U8-RD3-Pad41)") (class "Default")
      (node (ref "U8") (pin "41") (pinfunction "RD3_41") (pintype "bidirectional"))
    )
    (net (code "112") (name "unconnected-(U8-RD4-Pad2)") (class "Default")
      (node (ref "U8") (pin "2") (pinfunction "RD4_2") (pintype "bidirectional"))
    )
  )
)
